# Control.net
KiCad netlist of a schematic drawn in Altium Designer
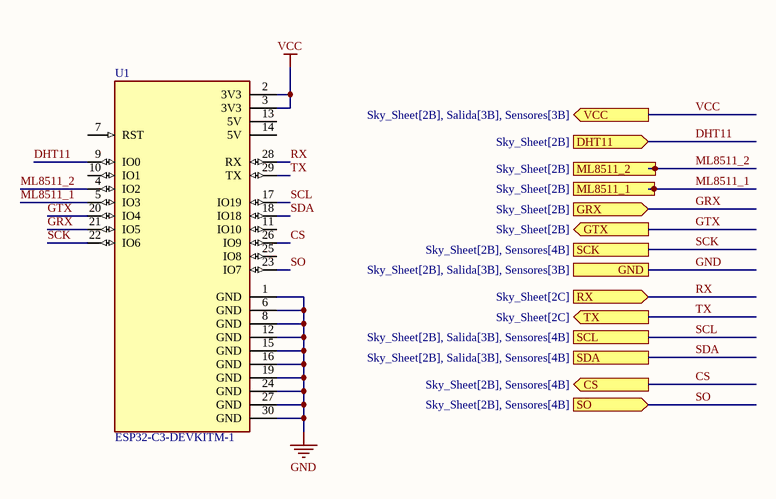
[diagram p0: Control.SchDoc]

(export (version "E")
  (design (tool "Eeschema 10.0.6"))
  (components
    (comp (ref "U1")
      (value "ESP32-C3-DEVKITM-1")
      (footprint "XCVR_ESP32-C3-DEVKITM-1")
      (fields (field (name "MF") "Espressif Systems"))
      (libsource (lib "ESP32-C3-DEVKITM-1") (part "ESP32-C3-DEVKITM-1"))
    )
  )
  (nets
    (net (code "1") (name "/CS") (class "Default")
      (node (ref "U1") (pin "26") (pinfunction "IO9_26") (pintype "bidirectional"))
    )
    (net (code "2") (name "/DHT11") (class "Default")
      (node (ref "U1") (pin "9") (pinfunction "IO0_9") (pintype "bidirectional"))
    )
    (net (code "3") (name "/GRX") (class "Default")
      (node (ref "U1") (pin "21") (pinfunction "IO5_21") (pintype "bidirectional"))
    )
    (net (code "4") (name "/GTX") (class "Default")
      (node (ref "U1") (pin "20") (pinfunction "IO4_20") (pintype "bidirectional"))
    )
    (net (code "5") (name "/ML8511_1") (class "Default")
      (node (ref "U1") (pin "5") (pinfunction "IO3_5") (pintype "bidirectional"))
    )
    (net (code "6") (name "/ML8511_2") (class "Default")
      (node (ref "U1") (pin "4") (pinfunction "IO2_4") (pintype "bidirectional"))
    )
    (net (code "7") (name "/RX") (class "Default")
      (node (ref "U1") (pin "28") (pinfunction "RX_28") (pintype "bidirectional"))
    )
    (net (code "8") (name "/SCK") (class "Default")
      (node (ref "U1") (pin "22") (pinfunction "IO6_22") (pintype "bidirectional"))
    )
    (net (code "9") (name "/SCL") (class "Default")
      (node (ref "U1") (pin "17") (pinfunction "IO19_17") (pintype "bidirectional"))
    )
    (net (code "10") (name "/SDA") (class "Default")
      (node (ref "U1") (pin "18") (pinfunction "IO18_18") (pintype "bidirectional"))
    )
    (net (code "11") (name "/SO") (class "Default")
      (node (ref "U1") (pin "23") (pinfunction "IO7_23") (pintype "bidirectional"))
    )
    (net (code "12") (name "/TX") (class "Default")
      (node (ref "U1") (pin "29") (pinfunction "TX_29") (pintype "bidirectional"))
    )
    (net (code "13") (name "GND") (class "Default")
      (node (ref "U1") (pin "1") (pinfunction "GND_1") (pintype "power_in"))
      (node (ref "U1") (pin "12") (pinfunction "GND_12") (pintype "power_in"))
      (node (ref "U1") (pin "15") (pinfunction "GND_15") (pintype "power_in"))
      (node (ref "U1") (pin "16") (pinfunction "GND_16") (pintype "power_in"))
      (node (ref "U1") (pin "19") (pinfunction "GND_19") (pintype "power_in"))
      (node (ref "U1") (pin "24") (pinfunction "GND_24") (pintype "power_in"))
      (node (ref "U1") (pin "27") (pinfunction "GND_27") (pintype "power_in"))
      (node (ref "U1") (pin "30") (pinfunction "GND_30") (pintype "power_in"))
      (node (ref "U1") (pin "6") (pinfunction "GND_6") (pintype "power_in"))
      (node (ref "U1") (pin "8") (pinfunction "GND_8") (pintype "power_in"))
    )
    (net (code "14") (name "VCC") (class "Default")
      (node (ref "U1") (pin "2") (pinfunction "3V3_2") (pintype "power_in"))
      (node (ref "U1") (pin "3") (pinfunction "3V3_3") (pintype "power_in"))
    )
    (net (code "15") (name "unconnected-(U1-5V-Pad13)") (class "Default")
      (node (ref "U1") (pin "13") (pinfunction "5V_13") (pintype "power_in"))
    )
    (net (code "16") (name "unconnected-(U1-5V-Pad14)") (class "Default")
      (node (ref "U1") (pin "14") (pinfunction "5V_14") (pintype "power_in"))
    )
    (net (code "17") (name "unconnected-(U1-IO1-Pad10)") (class "Default")
      (node (ref "U1") (pin "10") (pinfunction "IO1_10") (pintype "bidirectional"))
    )
    (net (code "18") (name "unconnected-(U1-IO8-Pad25)") (class "Default")
      (node (ref "U1") (pin "25") (pinfunction "IO8_25") (pintype "bidirectional"))
    )
    (net (code "19") (name "unconnected-(U1-IO10-Pad11)") (class "Default")
      (node (ref "U1") (pin "11") (pinfunction "IO10_11") (pintype "bidirectional"))
    )
    (net (code "20") (name "unconnected-(U1-RST-Pad7)") (class "Default")
      (node (ref "U1") (pin "7") (pinfunction "RST_7") (pintype "input"))
    )
  )
)
